# Precision_Arduino_Charlieplex_2_0.net
KiCad netlist of a schematic drawn in EAGLE
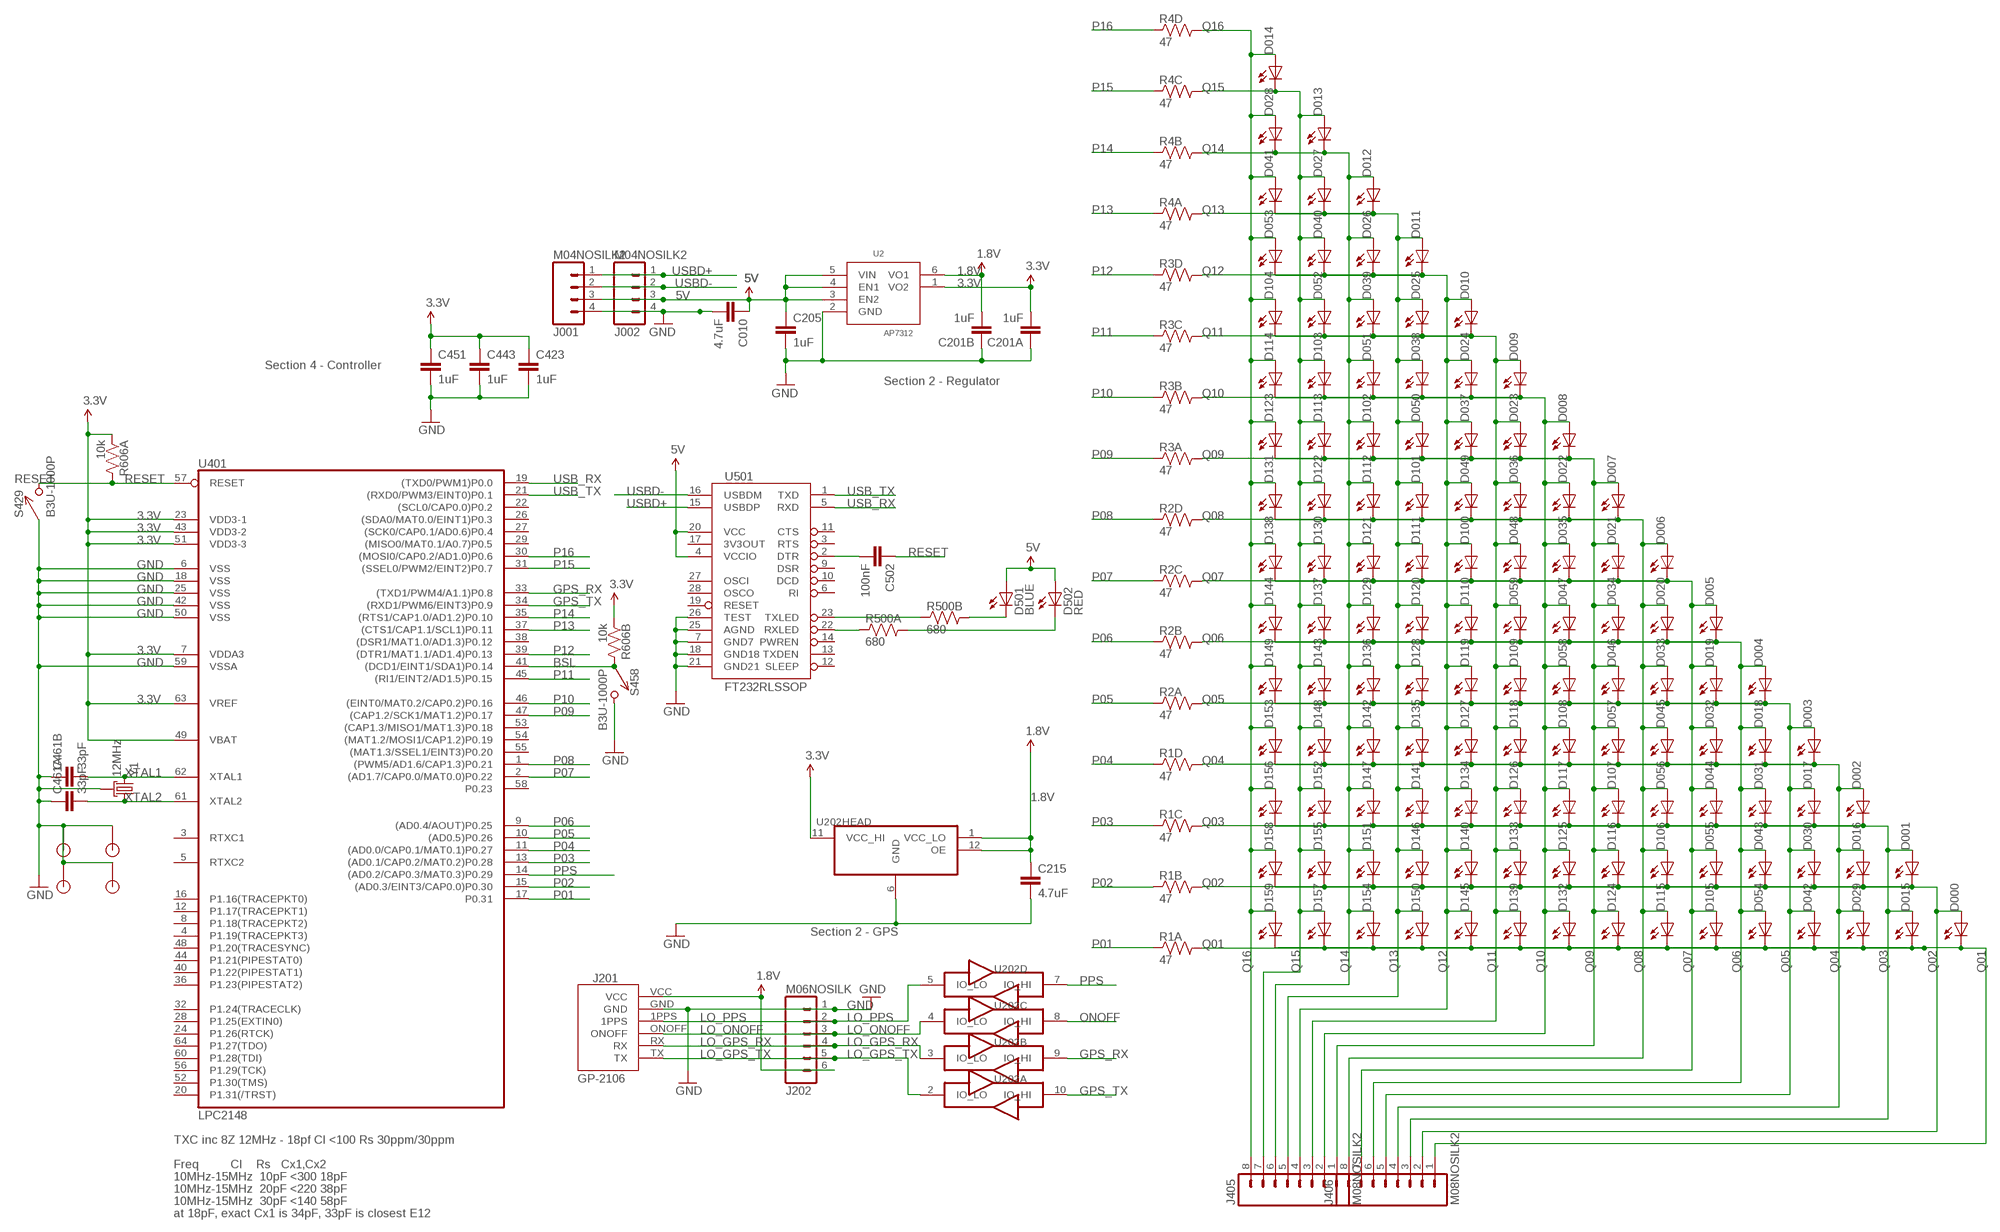
[diagram p0: schematic, sheet 1]

(export (version "E")
  (design (tool "Eeschema 10.0.6"))
  (components
    (comp (ref "C010")
      (value "4.7uF")
      (footprint "eagle-import:0603-CAP")
      (libsource (lib "eagle-import") (part "CAP0603-CAP"))
    )
    (comp (ref "C201")
      (value "1uF")
      (footprint "eagle-import:CKCM25")
      (libsource (lib "eagle-import") (part "CKCM25"))
    )
    (comp (ref "C205")
      (value "1uF")
      (footprint "eagle-import:0603-CAP")
      (libsource (lib "eagle-import") (part "SparkFun-Capacitors_CAP0603-CAP"))
    )
    (comp (ref "C215")
      (value "4.7uF")
      (footprint "eagle-import:0402-CAP")
      (libsource (lib "eagle-import") (part "CAP0402-CAP"))
    )
    (comp (ref "C423")
      (value "1uF")
      (footprint "eagle-import:0603-CAP")
      (libsource (lib "eagle-import") (part "SparkFun-Capacitors_CAP0603-CAP"))
    )
    (comp (ref "C443")
      (value "1uF")
      (footprint "eagle-import:0603-CAP")
      (libsource (lib "eagle-import") (part "SparkFun-Capacitors_CAP0603-CAP"))
    )
    (comp (ref "C451")
      (value "1uF")
      (footprint "eagle-import:0603-CAP")
      (libsource (lib "eagle-import") (part "SparkFun-Capacitors_CAP0603-CAP"))
    )
    (comp (ref "C461")
      (value "33pF")
      (footprint "eagle-import:CKCM25")
      (libsource (lib "eagle-import") (part "CKCM25"))
    )
    (comp (ref "C502")
      (value "100nF")
      (footprint "eagle-import:0603-CAP")
      (libsource (lib "eagle-import") (part "CAP0603-CAP"))
    )
    (comp (ref "D000")
      (value "HOUR")
      (footprint "eagle-import:LED-0603")
      (libsource (lib "eagle-import") (part "LED0603"))
    )
    (comp (ref "D001")
      (value "HOUR")
      (footprint "eagle-import:LED-0603")
      (libsource (lib "eagle-import") (part "LED0603"))
    )
    (comp (ref "D002")
      (value "HOUR")
      (footprint "eagle-import:LED-0603")
      (libsource (lib "eagle-import") (part "LED0603"))
    )
    (comp (ref "D003")
      (value "HOUR")
      (footprint "eagle-import:LED-0603")
      (libsource (lib "eagle-import") (part "LED0603"))
    )
    (comp (ref "D004")
      (value "HOUR")
      (footprint "eagle-import:LED-0603")
      (libsource (lib "eagle-import") (part "LED0603"))
    )
    (comp (ref "D005")
      (value "HOUR")
      (footprint "eagle-import:LED-0603")
      (libsource (lib "eagle-import") (part "LED0603"))
    )
    (comp (ref "D006")
      (value "HOUR")
      (footprint "eagle-import:LED-0603")
      (libsource (lib "eagle-import") (part "LED0603"))
    )
    (comp (ref "D007")
      (value "HOUR")
      (footprint "eagle-import:LED-0603")
      (libsource (lib "eagle-import") (part "LED0603"))
    )
    (comp (ref "D008")
      (value "HOUR")
      (footprint "eagle-import:LED-0603")
      (libsource (lib "eagle-import") (part "LED0603"))
    )
    (comp (ref "D009")
      (value "HOUR")
      (footprint "eagle-import:LED-0603")
      (libsource (lib "eagle-import") (part "LED0603"))
    )
    (comp (ref "D010")
      (value "HOUR")
      (footprint "eagle-import:LED-0603")
      (libsource (lib "eagle-import") (part "LED0603"))
    )
    (comp (ref "D011")
      (value "HOUR")
      (footprint "eagle-import:LED-0603")
      (libsource (lib "eagle-import") (part "LED0603"))
    )
    (comp (ref "D012")
      (value "HOUR")
      (footprint "eagle-import:LED-0603")
      (libsource (lib "eagle-import") (part "LED0603"))
    )
    (comp (ref "D013")
      (value "HOUR")
      (footprint "eagle-import:LED-0603")
      (libsource (lib "eagle-import") (part "LED0603"))
    )
    (comp (ref "D014")
      (value "HOUR")
      (footprint "eagle-import:LED-0603")
      (libsource (lib "eagle-import") (part "LED0603"))
    )
    (comp (ref "D015")
      (value "HOUR")
      (footprint "eagle-import:LED-0603")
      (libsource (lib "eagle-import") (part "LED0603"))
    )
    (comp (ref "D016")
      (value "HOUR")
      (footprint "eagle-import:LED-0603")
      (libsource (lib "eagle-import") (part "LED0603"))
    )
    (comp (ref "D017")
      (value "HOUR")
      (footprint "eagle-import:LED-0603")
      (libsource (lib "eagle-import") (part "LED0603"))
    )
    (comp (ref "D018")
      (value "HOUR")
      (footprint "eagle-import:LED-0603")
      (libsource (lib "eagle-import") (part "LED0603"))
    )
    (comp (ref "D019")
      (value "HOUR")
      (footprint "eagle-import:LED-0603")
      (libsource (lib "eagle-import") (part "LED0603"))
    )
    (comp (ref "D020")
      (value "HOUR")
      (footprint "eagle-import:LED-0603")
      (libsource (lib "eagle-import") (part "LED0603"))
    )
    (comp (ref "D021")
      (value "HOUR")
      (footprint "eagle-import:LED-0603")
      (libsource (lib "eagle-import") (part "LED0603"))
    )
    (comp (ref "D022")
      (value "HOUR")
      (footprint "eagle-import:LED-0603")
      (libsource (lib "eagle-import") (part "LED0603"))
    )
    (comp (ref "D023")
      (value "HOUR")
      (footprint "eagle-import:LED-0603")
      (libsource (lib "eagle-import") (part "LED0603"))
    )
    (comp (ref "D024")
      (value "HOUR")
      (footprint "eagle-import:LED-0603")
      (libsource (lib "eagle-import") (part "LED0603"))
    )
    (comp (ref "D025")
      (value "HOUR")
      (footprint "eagle-import:LED-0603")
      (libsource (lib "eagle-import") (part "LED0603"))
    )
    (comp (ref "D026")
      (value "HOUR")
      (footprint "eagle-import:LED-0603")
      (libsource (lib "eagle-import") (part "LED0603"))
    )
    (comp (ref "D027")
      (value "HOUR")
      (footprint "eagle-import:LED-0603")
      (libsource (lib "eagle-import") (part "LED0603"))
    )
    (comp (ref "D028")
      (value "HOUR")
      (footprint "eagle-import:LED-0603")
      (libsource (lib "eagle-import") (part "LED0603"))
    )
    (comp (ref "D029")
      (value "HOUR")
      (footprint "eagle-import:LED-0603")
      (libsource (lib "eagle-import") (part "LED0603"))
    )
    (comp (ref "D030")
      (value "HOUR")
      (footprint "eagle-import:LED-0603")
      (libsource (lib "eagle-import") (part "LED0603"))
    )
    (comp (ref "D031")
      (value "HOUR")
      (footprint "eagle-import:LED-0603")
      (libsource (lib "eagle-import") (part "LED0603"))
    )
    (comp (ref "D032")
      (value "HOUR")
      (footprint "eagle-import:LED-0603")
      (libsource (lib "eagle-import") (part "LED0603"))
    )
    (comp (ref "D033")
      (value "HOUR")
      (footprint "eagle-import:LED-0603")
      (libsource (lib "eagle-import") (part "LED0603"))
    )
    (comp (ref "D034")
      (value "HOUR")
      (footprint "eagle-import:LED-0603")
      (libsource (lib "eagle-import") (part "LED0603"))
    )
    (comp (ref "D035")
      (value "HOUR")
      (footprint "eagle-import:LED-0603")
      (libsource (lib "eagle-import") (part "LED0603"))
    )
    (comp (ref "D036")
      (value "HOUR")
      (footprint "eagle-import:LED-0603")
      (libsource (lib "eagle-import") (part "LED0603"))
    )
    (comp (ref "D037")
      (value "HOUR")
      (footprint "eagle-import:LED-0603")
      (libsource (lib "eagle-import") (part "LED0603"))
    )
    (comp (ref "D038")
      (value "HOUR")
      (footprint "eagle-import:LED-0603")
      (libsource (lib "eagle-import") (part "LED0603"))
    )
    (comp (ref "D039")
      (value "HOUR")
      (footprint "eagle-import:LED-0603")
      (libsource (lib "eagle-import") (part "LED0603"))
    )
    (comp (ref "D040")
      (value "HOUR")
      (footprint "eagle-import:LED-0603")
      (libsource (lib "eagle-import") (part "LED0603"))
    )
    (comp (ref "D041")
      (value "HOUR")
      (footprint "eagle-import:LED-0603")
      (libsource (lib "eagle-import") (part "LED0603"))
    )
    (comp (ref "D042")
      (value "HOUR")
      (footprint "eagle-import:LED-0603")
      (libsource (lib "eagle-import") (part "LED0603"))
    )
    (comp (ref "D043")
      (value "HOUR")
      (footprint "eagle-import:LED-0603")
      (libsource (lib "eagle-import") (part "LED0603"))
    )
    (comp (ref "D044")
      (value "HOUR")
      (footprint "eagle-import:LED-0603")
      (libsource (lib "eagle-import") (part "LED0603"))
    )
    (comp (ref "D045")
      (value "HOUR")
      (footprint "eagle-import:LED-0603")
      (libsource (lib "eagle-import") (part "LED0603"))
    )
    (comp (ref "D046")
      (value "HOUR")
      (footprint "eagle-import:LED-0603")
      (libsource (lib "eagle-import") (part "LED0603"))
    )
    (comp (ref "D047")
      (value "HOUR")
      (footprint "eagle-import:LED-0603")
      (libsource (lib "eagle-import") (part "LED0603"))
    )
    (comp (ref "D048")
      (value "HOUR")
      (footprint "eagle-import:LED-0603")
      (libsource (lib "eagle-import") (part "LED0603"))
    )
    (comp (ref "D049")
      (value "HOUR")
      (footprint "eagle-import:LED-0603")
      (libsource (lib "eagle-import") (part "LED0603"))
    )
    (comp (ref "D050")
      (value "HOUR")
      (footprint "eagle-import:LED-0603")
      (libsource (lib "eagle-import") (part "LED0603"))
    )
    (comp (ref "D051")
      (value "HOUR")
      (footprint "eagle-import:LED-0603")
      (libsource (lib "eagle-import") (part "LED0603"))
    )
    (comp (ref "D052")
      (value "HOUR")
      (footprint "eagle-import:LED-0603")
      (libsource (lib "eagle-import") (part "LED0603"))
    )
    (comp (ref "D053")
      (value "HOUR")
      (footprint "eagle-import:LED-0603")
      (libsource (lib "eagle-import") (part "LED0603"))
    )
    (comp (ref "D054")
      (value "HOUR")
      (footprint "eagle-import:LED-0603")
      (libsource (lib "eagle-import") (part "LED0603"))
    )
    (comp (ref "D055")
      (value "HOUR")
      (footprint "eagle-import:LED-0603")
      (libsource (lib "eagle-import") (part "LED0603"))
    )
    (comp (ref "D056")
      (value "HOUR")
      (footprint "eagle-import:LED-0603")
      (libsource (lib "eagle-import") (part "LED0603"))
    )
    (comp (ref "D057")
      (value "HOUR")
      (footprint "eagle-import:LED-0603")
      (libsource (lib "eagle-import") (part "LED0603"))
    )
    (comp (ref "D058")
      (value "HOUR")
      (footprint "eagle-import:LED-0603")
      (libsource (lib "eagle-import") (part "LED0603"))
    )
    (comp (ref "D059")
      (value "HOUR")
      (footprint "eagle-import:LED-0603")
      (libsource (lib "eagle-import") (part "LED0603"))
    )
    (comp (ref "D100")
      (value "HOUR")
      (footprint "eagle-import:LED-0603")
      (libsource (lib "eagle-import") (part "LED0603"))
    )
    (comp (ref "D101")
      (value "HOUR")
      (footprint "eagle-import:LED-0603")
      (libsource (lib "eagle-import") (part "LED0603"))
    )
    (comp (ref "D102")
      (value "HOUR")
      (footprint "eagle-import:LED-0603")
      (libsource (lib "eagle-import") (part "LED0603"))
    )
    (comp (ref "D103")
      (value "HOUR")
      (footprint "eagle-import:LED-0603")
      (libsource (lib "eagle-import") (part "LED0603"))
    )
    (comp (ref "D104")
      (value "HOUR")
      (footprint "eagle-import:LED-0603")
      (libsource (lib "eagle-import") (part "LED0603"))
    )
    (comp (ref "D105")
      (value "HOUR")
      (footprint "eagle-import:LED-0603")
      (libsource (lib "eagle-import") (part "LED0603"))
    )
    (comp (ref "D106")
      (value "HOUR")
      (footprint "eagle-import:LED-0603")
      (libsource (lib "eagle-import") (part "LED0603"))
    )
    (comp (ref "D107")
      (value "HOUR")
      (footprint "eagle-import:LED-0603")
      (libsource (lib "eagle-import") (part "LED0603"))
    )
    (comp (ref "D108")
      (value "HOUR")
      (footprint "eagle-import:LED-0603")
      (libsource (lib "eagle-import") (part "LED0603"))
    )
    (comp (ref "D109")
      (value "HOUR")
      (footprint "eagle-import:LED-0603")
      (libsource (lib "eagle-import") (part "LED0603"))
    )
    (comp (ref "D110")
      (value "HOUR")
      (footprint "eagle-import:LED-0603")
      (libsource (lib "eagle-import") (part "LED0603"))
    )
    (comp (ref "D111")
      (value "HOUR")
      (footprint "eagle-import:LED-0603")
      (libsource (lib "eagle-import") (part "LED0603"))
    )
    (comp (ref "D112")
      (value "HOUR")
      (footprint "eagle-import:LED-0603")
      (libsource (lib "eagle-import") (part "LED0603"))
    )
    (comp (ref "D113")
      (value "HOUR")
      (footprint "eagle-import:LED-0603")
      (libsource (lib "eagle-import") (part "LED0603"))
    )
    (comp (ref "D114")
      (value "HOUR")
      (footprint "eagle-import:LED-0603")
      (libsource (lib "eagle-import") (part "LED0603"))
    )
    (comp (ref "D115")
      (value "HOUR")
      (footprint "eagle-import:LED-0603")
      (libsource (lib "eagle-import") (part "LED0603"))
    )
    (comp (ref "D116")
      (value "HOUR")
      (footprint "eagle-import:LED-0603")
      (libsource (lib "eagle-import") (part "LED0603"))
    )
    (comp (ref "D117")
      (value "HOUR")
      (footprint "eagle-import:LED-0603")
      (libsource (lib "eagle-import") (part "LED0603"))
    )
    (comp (ref "D118")
      (value "HOUR")
      (footprint "eagle-import:LED-0603")
      (libsource (lib "eagle-import") (part "LED0603"))
    )
    (comp (ref "D119")
      (value "HOUR")
      (footprint "eagle-import:LED-0603")
      (libsource (lib "eagle-import") (part "LED0603"))
    )
    (comp (ref "D120")
      (value "HOUR")
      (footprint "eagle-import:LED-0603")
      (libsource (lib "eagle-import") (part "LED0603"))
    )
    (comp (ref "D121")
      (value "HOUR")
      (footprint "eagle-import:LED-0603")
      (libsource (lib "eagle-import") (part "LED0603"))
    )
    (comp (ref "D122")
      (value "HOUR")
      (footprint "eagle-import:LED-0603")
      (libsource (lib "eagle-import") (part "LED0603"))
    )
    (comp (ref "D123")
      (value "HOUR")
      (footprint "eagle-import:LED-0603")
      (libsource (lib "eagle-import") (part "LED0603"))
    )
    (comp (ref "D124")
      (value "HOUR")
      (footprint "eagle-import:LED-0603")
      (libsource (lib "eagle-import") (part "LED0603"))
    )
    (comp (ref "D125")
      (value "HOUR")
      (footprint "eagle-import:LED-0603")
      (libsource (lib "eagle-import") (part "LED0603"))
    )
    (comp (ref "D126")
      (value "HOUR")
      (footprint "eagle-import:LED-0603")
      (libsource (lib "eagle-import") (part "LED0603"))
    )
    (comp (ref "D127")
      (value "HOUR")
      (footprint "eagle-import:LED-0603")
      (libsource (lib "eagle-import") (part "LED0603"))
    )
    (comp (ref "D128")
      (value "HOUR")
      (footprint "eagle-import:LED-0603")
      (libsource (lib "eagle-import") (part "LED0603"))
    )
    (comp (ref "D129")
      (value "HOUR")
      (footprint "eagle-import:LED-0603")
      (libsource (lib "eagle-import") (part "LED0603"))
    )
    (comp (ref "D130")
      (value "HOUR")
      (footprint "eagle-import:LED-0603")
      (libsource (lib "eagle-import") (part "LED0603"))
    )
    (comp (ref "D131")
      (value "HOUR")
      (footprint "eagle-import:LED-0603")
      (libsource (lib "eagle-import") (part "LED0603"))
    )
    (comp (ref "D132")
      (value "HOUR")
      (footprint "eagle-import:LED-0603")
      (libsource (lib "eagle-import") (part "LED0603"))
    )
    (comp (ref "D133")
      (value "HOUR")
      (footprint "eagle-import:LED-0603")
      (libsource (lib "eagle-import") (part "LED0603"))
    )
    (comp (ref "D134")
      (value "HOUR")
      (footprint "eagle-import:LED-0603")
      (libsource (lib "eagle-import") (part "LED0603"))
    )
    (comp (ref "D135")
      (value "HOUR")
      (footprint "eagle-import:LED-0603")
      (libsource (lib "eagle-import") (part "LED0603"))
    )
    (comp (ref "D136")
      (value "HOUR")
      (footprint "eagle-import:LED-0603")
      (libsource (lib "eagle-import") (part "LED0603"))
    )
    (comp (ref "D137")
      (value "HOUR")
      (footprint "eagle-import:LED-0603")
      (libsource (lib "eagle-import") (part "LED0603"))
    )
    (comp (ref "D138")
      (value "HOUR")
      (footprint "eagle-import:LED-0603")
      (libsource (lib "eagle-import") (part "LED0603"))
    )
    (comp (ref "D139")
      (value "HOUR")
      (footprint "eagle-import:LED-0603")
      (libsource (lib "eagle-import") (part "LED0603"))
    )
    (comp (ref "D140")
      (value "HOUR")
      (footprint "eagle-import:LED-0603")
      (libsource (lib "eagle-import") (part "LED0603"))
    )
    (comp (ref "D141")
      (value "HOUR")
      (footprint "eagle-import:LED-0603")
      (libsource (lib "eagle-import") (part "LED0603"))
    )
    (comp (ref "D142")
      (value "HOUR")
      (footprint "eagle-import:LED-0603")
      (libsource (lib "eagle-import") (part "LED0603"))
    )
    (comp (ref "D143")
      (value "HOUR")
      (footprint "eagle-import:LED-0603")
      (libsource (lib "eagle-import") (part "LED0603"))
    )
    (comp (ref "D144")
      (value "HOUR")
      (footprint "eagle-import:LED-0603")
      (libsource (lib "eagle-import") (part "LED0603"))
    )
    (comp (ref "D145")
      (value "HOUR")
      (footprint "eagle-import:LED-0603")
      (libsource (lib "eagle-import") (part "LED0603"))
    )
    (comp (ref "D146")
      (value "HOUR")
      (footprint "eagle-import:LED-0603")
      (libsource (lib "eagle-import") (part "LED0603"))
    )
    (comp (ref "D147")
      (value "HOUR")
      (footprint "eagle-import:LED-0603")
      (libsource (lib "eagle-import") (part "LED0603"))
    )
    (comp (ref "D148")
      (value "HOUR")
      (footprint "eagle-import:LED-0603")
      (libsource (lib "eagle-import") (part "LED0603"))
    )
    (comp (ref "D149")
      (value "HOUR")
      (footprint "eagle-import:LED-0603")
      (libsource (lib "eagle-import") (part "LED0603"))
    )
    (comp (ref "D150")
      (value "HOUR")
      (footprint "eagle-import:LED-0603")
      (libsource (lib "eagle-import") (part "LED0603"))
    )
    (comp (ref "D151")
      (value "HOUR")
      (footprint "eagle-import:LED-0603")
      (libsource (lib "eagle-import") (part "LED0603"))
    )
    (comp (ref "D152")
      (value "HOUR")
      (footprint "eagle-import:LED-0603")
      (libsource (lib "eagle-import") (part "LED0603"))
    )
    (comp (ref "D153")
      (value "HOUR")
      (footprint "eagle-import:LED-0603")
      (libsource (lib "eagle-import") (part "LED0603"))
    )
    (comp (ref "D154")
      (value "HOUR")
      (footprint "eagle-import:LED-0603")
      (libsource (lib "eagle-import") (part "LED0603"))
    )
    (comp (ref "D155")
      (value "HOUR")
      (footprint "eagle-import:LED-0603")
      (libsource (lib "eagle-import") (part "LED0603"))
    )
    (comp (ref "D156")
      (value "HOUR")
      (footprint "eagle-import:LED-0603")
      (libsource (lib "eagle-import") (part "LED0603"))
    )
    (comp (ref "D157")
      (value "HOUR")
      (footprint "eagle-import:LED-0603")
      (libsource (lib "eagle-import") (part "LED0603"))
    )
    (comp (ref "D158")
      (value "HOUR")
      (footprint "eagle-import:LED-0603")
      (libsource (lib "eagle-import") (part "LED0603"))
    )
    (comp (ref "D159")
      (value "HOUR")
      (footprint "eagle-import:LED-0603")
      (libsource (lib "eagle-import") (part "LED0603"))
    )
    (comp (ref "D501")
      (value "BLUE")
      (footprint "eagle-import:LED-0603")
      (libsource (lib "eagle-import") (part "LED0603"))
    )
    (comp (ref "D502")
      (value "RED")
      (footprint "eagle-import:LED-0603")
      (libsource (lib "eagle-import") (part "LED0603"))
    )
    (comp (ref "J001")
      (value "M04NOSILK2")
      (footprint "eagle-import:1X04")
      (libsource (lib "eagle-import") (part "M04NOSILK2"))
    )
    (comp (ref "J002")
      (value "M04NOSILK2")
      (footprint "eagle-import:1X04")
      (libsource (lib "eagle-import") (part "M04NOSILK2"))
    )
    (comp (ref "J201")
      (value "GP-2106")
      (footprint "eagle-import:GP-2106")
      (libsource (lib "eagle-import") (part "GP-2106"))
    )
    (comp (ref "J202")
      (value "M06NOSILK")
      (footprint "eagle-import:M06SIP")
      (libsource (lib "eagle-import") (part "M06NOSILK"))
    )
    (comp (ref "J405")
      (value "M08NOSILK2")
      (footprint "eagle-import:1X08")
      (libsource (lib "eagle-import") (part "M08NOSILK2"))
    )
    (comp (ref "J406")
      (value "M08NOSILK2")
      (footprint "eagle-import:1X08")
      (libsource (lib "eagle-import") (part "M08NOSILK2"))
    )
    (comp (ref "JP1")
      (value "STANDOFF")
      (footprint "eagle-import:STANDOFF")
      (libsource (lib "eagle-import") (part "STANDOFF"))
    )
    (comp (ref "JP2")
      (value "STANDOFF")
      (footprint "eagle-import:STANDOFF")
      (libsource (lib "eagle-import") (part "STANDOFF"))
    )
    (comp (ref "JP3")
      (value "STANDOFF")
      (footprint "eagle-import:STANDOFF")
      (libsource (lib "eagle-import") (part "STANDOFF"))
    )
    (comp (ref "JP4")
      (value "STANDOFF")
      (footprint "eagle-import:STANDOFF")
      (libsource (lib "eagle-import") (part "STANDOFF"))
    )
    (comp (ref "R1")
      (value "47")
      (footprint "eagle-import:CRA04")
      (libsource (lib "eagle-import") (part "RP404"))
    )
    (comp (ref "R2")
      (value "47")
      (footprint "eagle-import:CRA04")
      (libsource (lib "eagle-import") (part "RP404"))
    )
    (comp (ref "R3")
      (value "47")
      (footprint "eagle-import:CRA04")
      (libsource (lib "eagle-import") (part "RP404"))
    )
    (comp (ref "R4")
      (value "47")
      (footprint "eagle-import:CRA04")
      (libsource (lib "eagle-import") (part "RP404"))
    )
    (comp (ref "R500")
      (value "680")
      (footprint "eagle-import:CRA02")
      (libsource (lib "eagle-import") (part "RP2EXB24V"))
    )
    (comp (ref "R606")
      (value "10k")
      (footprint "eagle-import:CRA02")
      (libsource (lib "eagle-import") (part "RP2EXB24V"))
    )
    (comp (ref "S429")
      (value "B3U-1000P")
      (footprint "eagle-import:B3U-1000P")
      (libsource (lib "eagle-import") (part "B3U-1000P"))
    )
    (comp (ref "S458")
      (value "B3U-1000P")
      (footprint "eagle-import:B3U-1000P")
      (libsource (lib "eagle-import") (part "B3U-1000P"))
    )
    (comp (ref "U2")
      (value "AP7312")
      (footprint "eagle-import:SOT-23-6")
      (libsource (lib "eagle-import") (part "AP73X2"))
    )
    (comp (ref "U202")
      (value "TXB0104RUT")
      (footprint "eagle-import:R-PUQFN-N12")
      (libsource (lib "eagle-import") (part "TXB0104RUT"))
    )
    (comp (ref "U401")
      (value "LPC2148")
      (footprint "eagle-import:SQFP-S-10X10-64")
      (libsource (lib "eagle-import") (part "LPC213X"))
    )
    (comp (ref "U501")
      (value "FT232RLSSOP")
      (footprint "eagle-import:SSOP28DB")
      (libsource (lib "eagle-import") (part "FT232RLSSOP"))
    )
    (comp (ref "Y1")
      (value "12MHz")
      (footprint "eagle-import:CRYSTAL_SMD_2MM_2_5MM")
      (libsource (lib "eagle-import") (part "CX2520"))
    )
  )
  (nets
    (net (code "1") (name "/BSL") (class "Default")
      (node (ref "R606") (pin "3") (pinfunction "2_3") (pintype "passive"))
      (node (ref "S458") (pin "P$1") (pinfunction "1_P$1") (pintype "bidirectional"))
      (node (ref "U401") (pin "41") (pinfunction "(DCD1/EINT1/SDA1)P0.14_41") (pintype "bidirectional"))
    )
    (net (code "2") (name "/GPS_RX") (class "Default")
      (node (ref "U202") (pin "9") (pinfunction "IO_HI_9") (pintype "bidirectional"))
      (node (ref "U401") (pin "33") (pinfunction "(TXD1/PWM4/A1.1)P0.8_33") (pintype "bidirectional"))
    )
    (net (code "3") (name "/GPS_TX") (class "Default")
      (node (ref "U202") (pin "10") (pinfunction "IO_HI_10") (pintype "bidirectional"))
      (node (ref "U401") (pin "34") (pinfunction "(RXD1/PWM6/EINT3)P0.9_34") (pintype "bidirectional"))
    )
    (net (code "4") (name "/LO_GPS_RX") (class "Default")
      (node (ref "J201") (pin "RX") (pinfunction "RX_RX") (pintype "bidirectional"))
      (node (ref "J202") (pin "4") (pinfunction "4_4") (pintype "passive"))
      (node (ref "U202") (pin "3") (pinfunction "IO_LO_3") (pintype "bidirectional"))
    )
    (net (code "5") (name "/LO_GPS_TX") (class "Default")
      (node (ref "J201") (pin "TX") (pinfunction "TX_TX") (pintype "bidirectional"))
      (node (ref "J202") (pin "5") (pinfunction "5_5") (pintype "passive"))
      (node (ref "U202") (pin "2") (pinfunction "IO_LO_2") (pintype "bidirectional"))
    )
    (net (code "6") (name "/LO_ONOFF") (class "Default")
      (node (ref "J201") (pin "ONOFF") (pinfunction "ONOFF_ONOFF") (pintype "bidirectional"))
      (node (ref "J202") (pin "3") (pinfunction "3_3") (pintype "passive"))
      (node (ref "U202") (pin "4") (pinfunction "IO_LO_4") (pintype "bidirectional"))
    )
    (net (code "7") (name "/LO_PPS") (class "Default")
      (node (ref "J201") (pin "1PPS") (pinfunction "1PPS_1PPS") (pintype "bidirectional"))
      (node (ref "J202") (pin "2") (pinfunction "2_2") (pintype "passive"))
      (node (ref "U202") (pin "5") (pinfunction "IO_LO_5") (pintype "bidirectional"))
    )
    (net (code "8") (name "/ONOFF") (class "Default")
      (node (ref "U202") (pin "8") (pinfunction "IO_HI_8") (pintype "bidirectional"))
    )
    (net (code "9") (name "/P01") (class "Default")
      (node (ref "R1") (pin "1") (pinfunction "1_1") (pintype "passive"))
      (node (ref "U401") (pin "17") (pinfunction "P0.31_17") (pintype "output"))
    )
    (net (code "10") (name "/P02") (class "Default")
      (node (ref "R1") (pin "2") (pinfunction "1_2") (pintype "passive"))
      (node (ref "U401") (pin "15") (pinfunction "(AD0.3/EINT3/CAP0.0)P0.30_15") (pintype "bidirectional"))
    )
    (net (code "11") (name "/P03") (class "Default")
      (node (ref "R1") (pin "3") (pinfunction "1_3") (pintype "passive"))
      (node (ref "U401") (pin "13") (pinfunction "(AD0.1/CAP0.2/MAT0.2)P0.28_13") (pintype "bidirectional"))
    )
    (net (code "12") (name "/P04") (class "Default")
      (node (ref "R1") (pin "4") (pinfunction "1_4") (pintype "passive"))
      (node (ref "U401") (pin "11") (pinfunction "(AD0.0/CAP0.1/MAT0.1)P0.27_11") (pintype "bidirectional"))
    )
    (net (code "13") (name "/P05") (class "Default")
      (node (ref "R2") (pin "1") (pinfunction "1_1") (pintype "passive"))
      (node (ref "U401") (pin "10") (pinfunction "(AD0.5)P0.26_10") (pintype "bidirectional"))
    )
    (net (code "14") (name "/P06") (class "Default")
      (node (ref "R2") (pin "2") (pinfunction "1_2") (pintype "passive"))
      (node (ref "U401") (pin "9") (pinfunction "(AD0.4/AOUT)P0.25_9") (pintype "bidirectional"))
    )
    (net (code "15") (name "/P07") (class "Default")
      (node (ref "R2") (pin "3") (pinfunction "1_3") (pintype "passive"))
      (node (ref "U401") (pin "2") (pinfunction "(AD1.7/CAP0.0/MAT0.0)P0.22_2") (pintype "bidirectional"))
    )
    (net (code "16") (name "/P08") (class "Default")
      (node (ref "R2") (pin "4") (pinfunction "1_4") (pintype "passive"))
      (node (ref "U401") (pin "1") (pinfunction "(PWM5/AD1.6/CAP1.3)P0.21_1") (pintype "bidirectional"))
    )
    (net (code "17") (name "/P09") (class "Default")
      (node (ref "R3") (pin "1") (pinfunction "1_1") (pintype "passive"))
      (node (ref "U401") (pin "47") (pinfunction "(CAP1.2/SCK1/MAT1.2)P0.17_47") (pintype "bidirectional"))
    )
    (net (code "18") (name "/P10") (class "Default")
      (node (ref "R3") (pin "2") (pinfunction "1_2") (pintype "passive"))
      (node (ref "U401") (pin "46") (pinfunction "(EINT0/MAT0.2/CAP0.2)P0.16_46") (pintype "bidirectional"))
    )
    (net (code "19") (name "/P11") (class "Default")
      (node (ref "R3") (pin "3") (pinfunction "1_3") (pintype "passive"))
      (node (ref "U401") (pin "45") (pinfunction "(RI1/EINT2/AD1.5)P0.15_45") (pintype "bidirectional"))
    )
    (net (code "20") (name "/P12") (class "Default")
      (node (ref "R3") (pin "4") (pinfunction "1_4") (pintype "passive"))
      (node (ref "U401") (pin "39") (pinfunction "(DTR1/MAT1.1/AD1.4)P0.13_39") (pintype "bidirectional"))
    )
    (net (code "21") (name "/P13") (class "Default")
      (node (ref "R4") (pin "1") (pinfunction "1_1") (pintype "passive"))
      (node (ref "U401") (pin "37") (pinfunction "(CTS1/CAP1.1/SCL1)P0.11_37") (pintype "bidirectional"))
    )
    (net (code "22") (name "/P14") (class "Default")
      (node (ref "R4") (pin "2") (pinfunction "1_2") (pintype "passive"))
      (node (ref "U401") (pin "35") (pinfunction "(RTS1/CAP1.0/AD1.2)P0.10_35") (pintype "bidirectional"))
    )
    (net (code "23") (name "/P15") (class "Default")
      (node (ref "R4") (pin "3") (pinfunction "1_3") (pintype "passive"))
      (node (ref "U401") (pin "31") (pinfunction "(SSEL0/PWM2/EINT2)P0.7_31") (pintype "bidirectional"))
    )
    (net (code "24") (name "/P16") (class "Default")
      (node (ref "R4") (pin "4") (pinfunction "1_4") (pintype "passive"))
      (node (ref "U401") (pin "30") (pinfunction "(MOSI0/CAP0.2/AD1.0)P0.6_30") (pintype "bidirectional"))
    )
    (net (code "25") (name "/PPS") (class "Default")
      (node (ref "U202") (pin "7") (pinfunction "IO_HI_7") (pintype "bidirectional"))
      (node (ref "U401") (pin "14") (pinfunction "(AD0.2/CAP0.3/MAT0.3)P0.29_14") (pintype "bidirectional"))
    )
    (net (code "26") (name "/Q01") (class "Default")
      (node (ref "D000") (pin "C") (pinfunction "C_C") (pintype "passive"))
      (node (ref "D015") (pin "C") (pinfunction "C_C") (pintype "passive"))
      (node (ref "D029") (pin "C") (pinfunction "C_C") (pintype "passive"))
      (node (ref "D042") (pin "C") (pinfunction "C_C") (pintype "passive"))
      (node (ref "D054") (pin "C") (pinfunction "C_C") (pintype "passive"))
      (node (ref "D105") (pin "C") (pinfunction "C_C") (pintype "passive"))
      (node (ref "D115") (pin "C") (pinfunction "C_C") (pintype "passive"))
      (node (ref "D124") (pin "C") (pinfunction "C_C") (pintype "passive"))
      (node (ref "D132") (pin "C") (pinfunction "C_C") (pintype "passive"))
      (node (ref "D139") (pin "C") (pinfunction "C_C") (pintype "passive"))
      (node (ref "D145") (pin "C") (pinfunction "C_C") (pintype "passive"))
      (node (ref "D150") (pin "C") (pinfunction "C_C") (pintype "passive"))
      (node (ref "D154") (pin "C") (pinfunction "C_C") (pintype "passive"))
      (node (ref "D157") (pin "C") (pinfunction "C_C") (pintype "passive"))
      (node (ref "D159") (pin "C") (pinfunction "C_C") (pintype "passive"))
      (node (ref "J406") (pin "1") (pinfunction "1_1") (pintype "passive"))
      (node (ref "R1") (pin "8") (pinfunction "2_8") (pintype "passive"))
    )
    (net (code "27") (name "/Q02") (class "Default")
      (node (ref "D000") (pin "A") (pinfunction "A_A") (pintype "passive"))
      (node (ref "D001") (pin "C") (pinfunction "C_C") (pintype "passive"))
      (node (ref "D016") (pin "C") (pinfunction "C_C") (pintype "passive"))
      (node (ref "D030") (pin "C") (pinfunction "C_C") (pintype "passive"))
      (node (ref "D043") (pin "C") (pinfunction "C_C") (pintype "passive"))
      (node (ref "D055") (pin "C") (pinfunction "C_C") (pintype "passive"))
      (node (ref "D106") (pin "C") (pinfunction "C_C") (pintype "passive"))
      (node (ref "D116") (pin "C") (pinfunction "C_C") (pintype "passive"))
      (node (ref "D125") (pin "C") (pinfunction "C_C") (pintype "passive"))
      (node (ref "D133") (pin "C") (pinfunction "C_C") (pintype "passive"))
      (node (ref "D140") (pin "C") (pinfunction "C_C") (pintype "passive"))
      (node (ref "D146") (pin "C") (pinfunction "C_C") (pintype "passive"))
      (node (ref "D151") (pin "C") (pinfunction "C_C") (pintype "passive"))
      (node (ref "D155") (pin "C") (pinfunction "C_C") (pintype "passive"))
      (node (ref "D158") (pin "C") (pinfunction "C_C") (pintype "passive"))
      (node (ref "J406") (pin "2") (pinfunction "2_2") (pintype "passive"))
      (node (ref "R1") (pin "7") (pinfunction "2_7") (pintype "passive"))
    )
    (net (code "28") (name "/Q03") (class "Default")
      (node (ref "D001") (pin "A") (pinfunction "A_A") (pintype "passive"))
      (node (ref "D002") (pin "C") (pinfunction "C_C") (pintype "passive"))
      (node (ref "D015") (pin "A") (pinfunction "A_A") (pintype "passive"))
      (node (ref "D017") (pin "C") (pinfunction "C_C") (pintype "passive"))
      (node (ref "D031") (pin "C") (pinfunction "C_C") (pintype "passive"))
      (node (ref "D044") (pin "C") (pinfunction "C_C") (pintype "passive"))
      (node (ref "D056") (pin "C") (pinfunction "C_C") (pintype "passive"))
      (node (ref "D107") (pin "C") (pinfunction "C_C") (pintype "passive"))
      (node (ref "D117") (pin "C") (pinfunction "C_C") (pintype "passive"))
      (node (ref "D126") (pin "C") (pinfunction "C_C") (pintype "passive"))
      (node (ref "D134") (pin "C") (pinfunction "C_C") (pintype "passive"))
      (node (ref "D141") (pin "C") (pinfunction "C_C") (pintype "passive"))
      (node (ref "D147") (pin "C") (pinfunction "C_C") (pintype "passive"))
      (node (ref "D152") (pin "C") (pinfunction "C_C") (pintype "passive"))
      (node (ref "D156") (pin "C") (pinfunction "C_C") (pintype "passive"))
      (node (ref "J406") (pin "3") (pinfunction "3_3") (pintype "passive"))
      (node (ref "R1") (pin "6") (pinfunction "2_6") (pintype "passive"))
    )
    (net (code "29") (name "/Q04") (class "Default")
      (node (ref "D002") (pin "A") (pinfunction "A_A") (pintype "passive"))
      (node (ref "D003") (pin "C") (pinfunction "C_C") (pintype "passive"))
      (node (ref "D016") (pin "A") (pinfunction "A_A") (pintype "passive"))
      (node (ref "D018") (pin "C") (pinfunction "C_C") (pintype "passive"))
      (node (ref "D029") (pin "A") (pinfunction "A_A") (pintype "passive"))
      (node (ref "D032") (pin "C") (pinfunction "C_C") (pintype "passive"))
      (node (ref "D045") (pin "C") (pinfunction "C_C") (pintype "passive"))
      (node (ref "D057") (pin "C") (pinfunction "C_C") (pintype "passive"))
      (node (ref "D108") (pin "C") (pinfunction "C_C") (pintype "passive"))
      (node (ref "D118") (pin "C") (pinfunction "C_C") (pintype "passive"))
      (node (ref "D127") (pin "C") (pinfunction "C_C") (pintype "passive"))
      (node (ref "D135") (pin "C") (pinfunction "C_C") (pintype "passive"))
      (node (ref "D142") (pin "C") (pinfunction "C_C") (pintype "passive"))
      (node (ref "D148") (pin "C") (pinfunction "C_C") (pintype "passive"))
      (node (ref "D153") (pin "C") (pinfunction "C_C") (pintype "passive"))
      (node (ref "J406") (pin "4") (pinfunction "4_4") (pintype "passive"))
      (node (ref "R1") (pin "5") (pinfunction "2_5") (pintype "passive"))
    )
    (net (code "30") (name "/Q05") (class "Default")
      (node (ref "D003") (pin "A") (pinfunction "A_A") (pintype "passive"))
      (node (ref "D004") (pin "C") (pinfunction "C_C") (pintype "passive"))
      (node (ref "D017") (pin "A") (pinfunction "A_A") (pintype "passive"))
      (node (ref "D019") (pin "C") (pinfunction "C_C") (pintype "passive"))
      (node (ref "D030") (pin "A") (pinfunction "A_A") (pintype "passive"))
      (node (ref "D033") (pin "C") (pinfunction "C_C") (pintype "passive"))
      (node (ref "D042") (pin "A") (pinfunction "A_A") (pintype "passive"))
      (node (ref "D046") (pin "C") (pinfunction "C_C") (pintype "passive"))
      (node (ref "D058") (pin "C") (pinfunction "C_C") (pintype "passive"))
      (node (ref "D109") (pin "C") (pinfunction "C_C") (pintype "passive"))
      (node (ref "D119") (pin "C") (pinfunction "C_C") (pintype "passive"))
      (node (ref "D128") (pin "C") (pinfunction "C_C") (pintype "passive"))
      (node (ref "D136") (pin "C") (pinfunction "C_C") (pintype "passive"))
      (node (ref "D143") (pin "C") (pinfunction "C_C") (pintype "passive"))
      (node (ref "D149") (pin "C") (pinfunction "C_C") (pintype "passive"))
      (node (ref "J406") (pin "5") (pinfunction "5_5") (pintype "passive"))
      (node (ref "R2") (pin "8") (pinfunction "2_8") (pintype "passive"))
    )
    (net (code "31") (name "/Q06") (class "Default")
      (node (ref "D004") (pin "A") (pinfunction "A_A") (pintype "passive"))
      (node (ref "D005") (pin "C") (pinfunction "C_C") (pintype "passive"))
      (node (ref "D018") (pin "A") (pinfunction "A_A") (pintype "passive"))
      (node (ref "D020") (pin "C") (pinfunction "C_C") (pintype "passive"))
      (node (ref "D031") (pin "A") (pinfunction "A_A") (pintype "passive"))
      (node (ref "D034") (pin "C") (pinfunction "C_C") (pintype "passive"))
      (node (ref "D043") (pin "A") (pinfunction "A_A") (pintype "passive"))
      (node (ref "D047") (pin "C") (pinfunction "C_C") (pintype "passive"))
      (node (ref "D054") (pin "A") (pinfunction "A_A") (pintype "passive"))
      (node (ref "D059") (pin "C") (pinfunction "C_C") (pintype "passive"))
      (node (ref "D110") (pin "C") (pinfunction "C_C") (pintype "passive"))
      (node (ref "D120") (pin "C") (pinfunction "C_C") (pintype "passive"))
      (node (ref "D129") (pin "C") (pinfunction "C_C") (pintype "passive"))
      (node (ref "D137") (pin "C") (pinfunction "C_C") (pintype "passive"))
      (node (ref "D144") (pin "C") (pinfunction "C_C") (pintype "passive"))
      (node (ref "J406") (pin "6") (pinfunction "6_6") (pintype "passive"))
      (node (ref "R2") (pin "7") (pinfunction "2_7") (pintype "passive"))
    )
    (net (code "32") (name "/Q07") (class "Default")
      (node (ref "D005") (pin "A") (pinfunction "A_A") (pintype "passive"))
      (node (ref "D006") (pin "C") (pinfunction "C_C") (pintype "passive"))
      (node (ref "D019") (pin "A") (pinfunction "A_A") (pintype "passive"))
      (node (ref "D021") (pin "C") (pinfunction "C_C") (pintype "passive"))
      (node (ref "D032") (pin "A") (pinfunction "A_A") (pintype "passive"))
      (node (ref "D035") (pin "C") (pinfunction "C_C") (pintype "passive"))
      (node (ref "D044") (pin "A") (pinfunction "A_A") (pintype "passive"))
      (node (ref "D048") (pin "C") (pinfunction "C_C") (pintype "passive"))
      (node (ref "D055") (pin "A") (pinfunction "A_A") (pintype "passive"))
      (node (ref "D100") (pin "C") (pinfunction "C_C") (pintype "passive"))
      (node (ref "D105") (pin "A") (pinfunction "A_A") (pintype "passive"))
      (node (ref "D111") (pin "C") (pinfunction "C_C") (pintype "passive"))
      (node (ref "D121") (pin "C") (pinfunction "C_C") (pintype "passive"))
      (node (ref "D130") (pin "C") (pinfunction "C_C") (pintype "passive"))
      (node (ref "D138") (pin "C") (pinfunction "C_C") (pintype "passive"))
      (node (ref "J406") (pin "7") (pinfunction "7_7") (pintype "passive"))
      (node (ref "R2") (pin "6") (pinfunction "2_6") (pintype "passive"))
    )
    (net (code "33") (name "/Q08") (class "Default")
      (node (ref "D006") (pin "A") (pinfunction "A_A") (pintype "passive"))
      (node (ref "D007") (pin "C") (pinfunction "C_C") (pintype "passive"))
      (node (ref "D020") (pin "A") (pinfunction "A_A") (pintype "passive"))
      (node (ref "D022") (pin "C") (pinfunction "C_C") (pintype "passive"))
      (node (ref "D033") (pin "A") (pinfunction "A_A") (pintype "passive"))
      (node (ref "D036") (pin "C") (pinfunction "C_C") (pintype "passive"))
      (node (ref "D045") (pin "A") (pinfunction "A_A") (pintype "passive"))
      (node (ref "D049") (pin "C") (pinfunction "C_C") (pintype "passive"))
      (node (ref "D056") (pin "A") (pinfunction "A_A") (pintype "passive"))
      (node (ref "D101") (pin "C") (pinfunction "C_C") (pintype "passive"))
      (node (ref "D106") (pin "A") (pinfunction "A_A") (pintype "passive"))
      (node (ref "D112") (pin "C") (pinfunction "C_C") (pintype "passive"))
      (node (ref "D115") (pin "A") (pinfunction "A_A") (pintype "passive"))
      (node (ref "D122") (pin "C") (pinfunction "C_C") (pintype "passive"))
      (node (ref "D131") (pin "C") (pinfunction "C_C") (pintype "passive"))
      (node (ref "J406") (pin "8") (pinfunction "8_8") (pintype "passive"))
      (node (ref "R2") (pin "5") (pinfunction "2_5") (pintype "passive"))
    )
    (net (code "34") (name "/Q09") (class "Default")
      (node (ref "D007") (pin "A") (pinfunction "A_A") (pintype "passive"))
      (node (ref "D008") (pin "C") (pinfunction "C_C") (pintype "passive"))
      (node (ref "D021") (pin "A") (pinfunction "A_A") (pintype "passive"))
      (node (ref "D023") (pin "C") (pinfunction "C_C") (pintype "passive"))
      (node (ref "D034") (pin "A") (pinfunction "A_A") (pintype "passive"))
      (node (ref "D037") (pin "C") (pinfunction "C_C") (pintype "passive"))
      (node (ref "D046") (pin "A") (pinfunction "A_A") (pintype "passive"))
      (node (ref "D050") (pin "C") (pinfunction "C_C") (pintype "passive"))
      (node (ref "D057") (pin "A") (pinfunction "A_A") (pintype "passive"))
      (node (ref "D102") (pin "C") (pinfunction "C_C") (pintype "passive"))
      (node (ref "D107") (pin "A") (pinfunction "A_A") (pintype "passive"))
      (node (ref "D113") (pin "C") (pinfunction "C_C") (pintype "passive"))
      (node (ref "D116") (pin "A") (pinfunction "A_A") (pintype "passive"))
      (node (ref "D123") (pin "C") (pinfunction "C_C") (pintype "passive"))
      (node (ref "D124") (pin "A") (pinfunction "A_A") (pintype "passive"))
      (node (ref "J405") (pin "1") (pinfunction "1_1") (pintype "passive"))
      (node (ref "R3") (pin "8") (pinfunction "2_8") (pintype "passive"))
    )
    (net (code "35") (name "/Q10") (class "Default")
      (node (ref "D008") (pin "A") (pinfunction "A_A") (pintype "passive"))
      (node (ref "D009") (pin "C") (pinfunction "C_C") (pintype "passive"))
      (node (ref "D022") (pin "A") (pinfunction "A_A") (pintype "passive"))
      (node (ref "D024") (pin "C") (pinfunction "C_C") (pintype "passive"))
      (node (ref "D035") (pin "A") (pinfunction "A_A") (pintype "passive"))
      (node (ref "D038") (pin "C") (pinfunction "C_C") (pintype "passive"))
      (node (ref "D047") (pin "A") (pinfunction "A_A") (pintype "passive"))
      (node (ref "D051") (pin "C") (pinfunction "C_C") (pintype "passive"))
      (node (ref "D058") (pin "A") (pinfunction "A_A") (pintype "passive"))
      (node (ref "D103") (pin "C") (pinfunction "C_C") (pintype "passive"))
      (node (ref "D108") (pin "A") (pinfunction "A_A") (pintype "passive"))
      (node (ref "D114") (pin "C") (pinfunction "C_C") (pintype "passive"))
      (node (ref "D117") (pin "A") (pinfunction "A_A") (pintype "passive"))
      (node (ref "D125") (pin "A") (pinfunction "A_A") (pintype "passive"))
      (node (ref "D132") (pin "A") (pinfunction "A_A") (pintype "passive"))
      (node (ref "J405") (pin "2") (pinfunction "2_2") (pintype "passive"))
      (node (ref "R3") (pin "7") (pinfunction "2_7") (pintype "passive"))
    )
    (net (code "36") (name "/Q11") (class "Default")
      (node (ref "D009") (pin "A") (pinfunction "A_A") (pintype "passive"))
      (node (ref "D010") (pin "C") (pinfunction "C_C") (pintype "passive"))
      (node (ref "D023") (pin "A") (pinfunction "A_A") (pintype "passive"))
      (node (ref "D025") (pin "C") (pinfunction "C_C") (pintype "passive"))
      (node (ref "D036") (pin "A") (pinfunction "A_A") (pintype "passive"))
      (node (ref "D039") (pin "C") (pinfunction "C_C") (pintype "passive"))
      (node (ref "D048") (pin "A") (pinfunction "A_A") (pintype "passive"))
      (node (ref "D052") (pin "C") (pinfunction "C_C") (pintype "passive"))
      (node (ref "D059") (pin "A") (pinfunction "A_A") (pintype "passive"))
      (node (ref "D104") (pin "C") (pinfunction "C_C") (pintype "passive"))
      (node (ref "D109") (pin "A") (pinfunction "A_A") (pintype "passive"))
      (node (ref "D118") (pin "A") (pinfunction "A_A") (pintype "passive"))
      (node (ref "D126") (pin "A") (pinfunction "A_A") (pintype "passive"))
      (node (ref "D133") (pin "A") (pinfunction "A_A") (pintype "passive"))
      (node (ref "D139") (pin "A") (pinfunction "A_A") (pintype "passive"))
      (node (ref "J405") (pin "3") (pinfunction "3_3") (pintype "passive"))
      (node (ref "R3") (pin "6") (pinfunction "2_6") (pintype "passive"))
    )
    (net (code "37") (name "/Q12") (class "Default")
      (node (ref "D010") (pin "A") (pinfunction "A_A") (pintype "passive"))
      (node (ref "D011") (pin "C") (pinfunction "C_C") (pintype "passive"))
      (node (ref "D024") (pin "A") (pinfunction "A_A") (pintype "passive"))
      (node (ref "D026") (pin "C") (pinfunction "C_C") (pintype "passive"))
      (node (ref "D037") (pin "A") (pinfunction "A_A") (pintype "passive"))
      (node (ref "D040") (pin "C") (pinfunction "C_C") (pintype "passive"))
      (node (ref "D049") (pin "A") (pinfunction "A_A") (pintype "passive"))
      (node (ref "D053") (pin "C") (pinfunction "C_C") (pintype "passive"))
      (node (ref "D100") (pin "A") (pinfunction "A_A") (pintype "passive"))
      (node (ref "D110") (pin "A") (pinfunction "A_A") (pintype "passive"))
      (node (ref "D119") (pin "A") (pinfunction "A_A") (pintype "passive"))
      (node (ref "D127") (pin "A") (pinfunction "A_A") (pintype "passive"))
      (node (ref "D134") (pin "A") (pinfunction "A_A") (pintype "passive"))
      (node (ref "D140") (pin "A") (pinfunction "A_A") (pintype "passive"))
      (node (ref "D145") (pin "A") (pinfunction "A_A") (pintype "passive"))
      (node (ref "J405") (pin "4") (pinfunction "4_4") (pintype "passive"))
      (node (ref "R3") (pin "5") (pinfunction "2_5") (pintype "passive"))
    )
    (net (code "38") (name "/Q13") (class "Default")
      (node (ref "D011") (pin "A") (pinfunction "A_A") (pintype "passive"))
      (node (ref "D012") (pin "C") (pinfunction "C_C") (pintype "passive"))
      (node (ref "D025") (pin "A") (pinfunction "A_A") (pintype "passive"))
      (node (ref "D027") (pin "C") (pinfunction "C_C") (pintype "passive"))
      (node (ref "D038") (pin "A") (pinfunction "A_A") (pintype "passive"))
      (node (ref "D041") (pin "C") (pinfunction "C_C") (pintype "passive"))
      (node (ref "D050") (pin "A") (pinfunction "A_A") (pintype "passive"))
      (node (ref "D101") (pin "A") (pinfunction "A_A") (pintype "passive"))
      (node (ref "D111") (pin "A") (pinfunction "A_A") (pintype "passive"))
      (node (ref "D120") (pin "A") (pinfunction "A_A") (pintype "passive"))
      (node (ref "D128") (pin "A") (pinfunction "A_A") (pintype "passive"))
      (node (ref "D135") (pin "A") (pinfunction "A_A") (pintype "passive"))
      (node (ref "D141") (pin "A") (pinfunction "A_A") (pintype "passive"))
      (node (ref "D146") (pin "A") (pinfunction "A_A") (pintype "passive"))
      (node (ref "D150") (pin "A") (pinfunction "A_A") (pintype "passive"))
      (node (ref "J405") (pin "5") (pinfunction "5_5") (pintype "passive"))
      (node (ref "R4") (pin "8") (pinfunction "2_8") (pintype "passive"))
    )
    (net (code "39") (name "/Q14") (class "Default")
      (node (ref "D012") (pin "A") (pinfunction "A_A") (pintype "passive"))
      (node (ref "D013") (pin "C") (pinfunction "C_C") (pintype "passive"))
      (node (ref "D026") (pin "A") (pinfunction "A_A") (pintype "passive"))
      (node (ref "D028") (pin "C") (pinfunction "C_C") (pintype "passive"))
      (node (ref "D039") (pin "A") (pinfunction "A_A") (pintype "passive"))
      (node (ref "D051") (pin "A") (pinfunction "A_A") (pintype "passive"))
      (node (ref "D102") (pin "A") (pinfunction "A_A") (pintype "passive"))
      (node (ref "D112") (pin "A") (pinfunction "A_A") (pintype "passive"))
      (node (ref "D121") (pin "A") (pinfunction "A_A") (pintype "passive"))
      (node (ref "D129") (pin "A") (pinfunction "A_A") (pintype "passive"))
      (node (ref "D136") (pin "A") (pinfunction "A_A") (pintype "passive"))
      (node (ref "D142") (pin "A") (pinfunction "A_A") (pintype "passive"))
      (node (ref "D147") (pin "A") (pinfunction "A_A") (pintype "passive"))
      (node (ref "D151") (pin "A") (pinfunction "A_A") (pintype "passive"))
      (node (ref "D154") (pin "A") (pinfunction "A_A") (pintype "passive"))
      (node (ref "J405") (pin "6") (pinfunction "6_6") (pintype "passive"))
      (node (ref "R4") (pin "7") (pinfunction "2_7") (pintype "passive"))
    )
    (net (code "40") (name "/Q15") (class "Default")
      (node (ref "D013") (pin "A") (pinfunction "A_A") (pintype "passive"))
      (node (ref "D014") (pin "C") (pinfunction "C_C") (pintype "passive"))
      (node (ref "D027") (pin "A") (pinfunction "A_A") (pintype "passive"))
      (node (ref "D040") (pin "A") (pinfunction "A_A") (pintype "passive"))
      (node (ref "D052") (pin "A") (pinfunction "A_A") (pintype "passive"))
      (node (ref "D103") (pin "A") (pinfunction "A_A") (pintype "passive"))
      (node (ref "D113") (pin "A") (pinfunction "A_A") (pintype "passive"))
      (node (ref "D122") (pin "A") (pinfunction "A_A") (pintype "passive"))
      (node (ref "D130") (pin "A") (pinfunction "A_A") (pintype "passive"))
      (node (ref "D137") (pin "A") (pinfunction "A_A") (pintype "passive"))
      (node (ref "D143") (pin "A") (pinfunction "A_A") (pintype "passive"))
      (node (ref "D148") (pin "A") (pinfunction "A_A") (pintype "passive"))
      (node (ref "D152") (pin "A") (pinfunction "A_A") (pintype "passive"))
      (node (ref "D155") (pin "A") (pinfunction "A_A") (pintype "passive"))
      (node (ref "D157") (pin "A") (pinfunction "A_A") (pintype "passive"))
      (node (ref "J405") (pin "7") (pinfunction "7_7") (pintype "passive"))
      (node (ref "R4") (pin "6") (pinfunction "2_6") (pintype "passive"))
    )
    (net (code "41") (name "/Q16") (class "Default")
      (node (ref "D014") (pin "A") (pinfunction "A_A") (pintype "passive"))
      (node (ref "D028") (pin "A") (pinfunction "A_A") (pintype "passive"))
      (node (ref "D041") (pin "A") (pinfunction "A_A") (pintype "passive"))
      (node (ref "D053") (pin "A") (pinfunction "A_A") (pintype "passive"))
      (node (ref "D104") (pin "A") (pinfunction "A_A") (pintype "passive"))
      (node (ref "D114") (pin "A") (pinfunction "A_A") (pintype "passive"))
      (node (ref "D123") (pin "A") (pinfunction "A_A") (pintype "passive"))
      (node (ref "D131") (pin "A") (pinfunction "A_A") (pintype "passive"))
      (node (ref "D138") (pin "A") (pinfunction "A_A") (pintype "passive"))
      (node (ref "D144") (pin "A") (pinfunction "A_A") (pintype "passive"))
      (node (ref "D149") (pin "A") (pinfunction "A_A") (pintype "passive"))
      (node (ref "D153") (pin "A") (pinfunction "A_A") (pintype "passive"))
      (node (ref "D156") (pin "A") (pinfunction "A_A") (pintype "passive"))
      (node (ref "D158") (pin "A") (pinfunction "A_A") (pintype "passive"))
      (node (ref "D159") (pin "A") (pinfunction "A_A") (pintype "passive"))
      (node (ref "J405") (pin "8") (pinfunction "8_8") (pintype "passive"))
      (node (ref "R4") (pin "5") (pinfunction "2_5") (pintype "passive"))
    )
    (net (code "42") (name "/RESET") (class "Default")
      (node (ref "C502") (pin "1") (pinfunction "1_1") (pintype "passive"))
      (node (ref "R606") (pin "4") (pinfunction "2_4") (pintype "passive"))
      (node (ref "S429") (pin "P$2") (pinfunction "2_P$2") (pintype "bidirectional"))
      (node (ref "U401") (pin "57") (pinfunction "RESET_57") (pintype "input"))
    )
    (net (code "43") (name "/USBD+") (class "Default")
      (node (ref "J001") (pin "1") (pinfunction "1_1") (pintype "passive"))
      (node (ref "J002") (pin "1") (pinfunction "1_1") (pintype "passive"))
      (node (ref "U501") (pin "15") (pinfunction "USBDP_15") (pintype "bidirectional"))
    )
    (net (code "44") (name "/USBD-") (class "Default")
      (node (ref "J001") (pin "2") (pinfunction "2_2") (pintype "passive"))
      (node (ref "J002") (pin "2") (pinfunction "2_2") (pintype "passive"))
      (node (ref "U501") (pin "16") (pinfunction "USBDM_16") (pintype "bidirectional"))
    )
    (net (code "45") (name "/USB_RX") (class "Default")
      (node (ref "U401") (pin "19") (pinfunction "(TXD0/PWM1)P0.0_19") (pintype "bidirectional"))
      (node (ref "U501") (pin "5") (pinfunction "RXD_5") (pintype "input"))
    )
    (net (code "46") (name "/USB_TX") (class "Default")
      (node (ref "U401") (pin "21") (pinfunction "(RXD0/PWM3/EINT0)P0.1_21") (pintype "bidirectional"))
      (node (ref "U501") (pin "1") (pinfunction "TXD_1") (pintype "output"))
    )
    (net (code "47") (name "/XTAL1") (class "Default")
      (node (ref "C461") (pin "3") (pinfunction "2_3") (pintype "passive"))
      (node (ref "U401") (pin "62") (pinfunction "XTAL1_62") (pintype "input"))
      (node (ref "Y1") (pin "3") (pinfunction "2_3") (pintype "passive"))
    )
    (net (code "48") (name "/XTAL2") (class "Default")
      (node (ref "C461") (pin "4") (pinfunction "2_4") (pintype "passive"))
      (node (ref "U401") (pin "61") (pinfunction "XTAL2_61") (pintype "output"))
      (node (ref "Y1") (pin "1") (pinfunction "1_1") (pintype "passive"))
    )
    (net (code "49") (name "1.8V") (class "Default")
      (node (ref "C201") (pin "3") (pinfunction "2_3") (pintype "passive"))
      (node (ref "C215") (pin "1") (pinfunction "1_1") (pintype "passive"))
      (node (ref "J201") (pin "VCC") (pinfunction "VCC_VCC") (pintype "bidirectional"))
      (node (ref "J202") (pin "6") (pinfunction "6_6") (pintype "passive"))
      (node (ref "U2") (pin "6") (pinfunction "VO1_6") (pintype "bidirectional"))
      (node (ref "U202") (pin "1") (pinfunction "VCC_LO_1") (pintype "power_in"))
      (node (ref "U202") (pin "12") (pinfunction "OE_12") (pintype "bidirectional"))
    )
    (net (code "50") (name "3.3V") (class "Default")
      (node (ref "C201") (pin "4") (pinfunction "2_4") (pintype "passive"))
      (node (ref "C423") (pin "1") (pinfunction "1_1") (pintype "passive"))
      (node (ref "C443") (pin "1") (pinfunction "1_1") (pintype "passive"))
      (node (ref "C451") (pin "1") (pinfunction "1_1") (pintype "passive"))
      (node (ref "R606") (pin "1") (pinfunction "1_1") (pintype "passive"))
      (node (ref "R606") (pin "2") (pinfunction "1_2") (pintype "passive"))
      (node (ref "U2") (pin "1") (pinfunction "VO2_1") (pintype "bidirectional"))
      (node (ref "U202") (pin "11") (pinfunction "VCC_HI_11") (pintype "power_in"))
      (node (ref "U401") (pin "23") (pinfunction "VDD3-1_23") (pintype "power_in"))
      (node (ref "U401") (pin "43") (pinfunction "VDD3-2_43") (pintype "power_in"))
      (node (ref "U401") (pin "49") (pinfunction "VBAT_49") (pintype "power_in"))
      (node (ref "U401") (pin "51") (pinfunction "VDD3-3_51") (pintype "power_in"))
      (node (ref "U401") (pin "63") (pinfunction "VREF_63") (pintype "input"))
      (node (ref "U401") (pin "7") (pinfunction "VDDA3_7") (pintype "power_in"))
    )
    (net (code "51") (name "5V") (class "Default")
      (node (ref "C010") (pin "1") (pinfunction "1_1") (pintype "passive"))
      (node (ref "C205") (pin "1") (pinfunction "1_1") (pintype "passive"))
      (node (ref "D501") (pin "A") (pinfunction "A_A") (pintype "passive"))
      (node (ref "D502") (pin "A") (pinfunction "A_A") (pintype "passive"))
      (node (ref "J001") (pin "3") (pinfunction "3_3") (pintype "passive"))
      (node (ref "J002") (pin "3") (pinfunction "3_3") (pintype "passive"))
      (node (ref "U2") (pin "3") (pinfunction "EN2_3") (pintype "bidirectional"))
      (node (ref "U2") (pin "4") (pinfunction "EN1_4") (pintype "bidirectional"))
      (node (ref "U2") (pin "5") (pinfunction "VIN_5") (pintype "bidirectional"))
      (node (ref "U501") (pin "20") (pinfunction "VCC_20") (pintype "power_in"))
      (node (ref "U501") (pin "4") (pinfunction "VCCIO_4") (pintype "power_in"))
    )
    (net (code "52") (name "GND") (class "Default")
      (node (ref "C010") (pin "2") (pinfunction "2_2") (pintype "passive"))
      (node (ref "C201") (pin "1") (pinfunction "1_1") (pintype "passive"))
      (node (ref "C201") (pin "2") (pinfunction "1_2") (pintype "passive"))
      (node (ref "C205") (pin "2") (pinfunction "2_2") (pintype "passive"))
      (node (ref "C215") (pin "2") (pinfunction "2_2") (pintype "passive"))
      (node (ref "C423") (pin "2") (pinfunction "2_2") (pintype "passive"))
      (node (ref "C443") (pin "2") (pinfunction "2_2") (pintype "passive"))
      (node (ref "C451") (pin "2") (pinfunction "2_2") (pintype "passive"))
      (node (ref "C461") (pin "1") (pinfunction "1_1") (pintype "passive"))
      (node (ref "C461") (pin "2") (pinfunction "1_2") (pintype "passive"))
      (node (ref "J001") (pin "4") (pinfunction "4_4") (pintype "passive"))
      (node (ref "J002") (pin "4") (pinfunction "4_4") (pintype "passive"))
      (node (ref "J201") (pin "GND") (pinfunction "GND_GND") (pintype "bidirectional"))
      (node (ref "J202") (pin "1") (pinfunction "1_1") (pintype "passive"))
      (node (ref "JP1") (pin "P$1") (pinfunction "P$1_P$1") (pintype "bidirectional"))
      (node (ref "JP2") (pin "P$1") (pinfunction "P$1_P$1") (pintype "bidirectional"))
      (node (ref "JP3") (pin "P$1") (pinfunction "P$1_P$1") (pintype "bidirectional"))
      (node (ref "JP4") (pin "P$1") (pinfunction "P$1_P$1") (pintype "bidirectional"))
      (node (ref "S429") (pin "P$1") (pinfunction "1_P$1") (pintype "bidirectional"))
      (node (ref "S458") (pin "P$2") (pinfunction "2_P$2") (pintype "bidirectional"))
      (node (ref "U2") (pin "2") (pinfunction "GND_2") (pintype "bidirectional"))
      (node (ref "U202") (pin "6") (pinfunction "GND_6") (pintype "power_in"))
      (node (ref "U401") (pin "18") (pinfunction "VSS_18") (pintype "power_in"))
      (node (ref "U401") (pin "25") (pinfunction "VSS_25") (pintype "power_in"))
      (node (ref "U401") (pin "42") (pinfunction "VSS_42") (pintype "power_in"))
      (node (ref "U401") (pin "50") (pinfunction "VSS_50") (pintype "power_in"))
      (node (ref "U401") (pin "59") (pinfunction "VSSA_59") (pintype "power_in"))
      (node (ref "U401") (pin "6") (pinfunction "VSS_6") (pintype "power_in"))
      (node (ref "U501") (pin "18") (pinfunction "GND18_18") (pintype "power_in"))
      (node (ref "U501") (pin "21") (pinfunction "GND21_21") (pintype "power_in"))
      (node (ref "U501") (pin "25") (pinfunction "AGND_25") (pintype "power_in"))
      (node (ref "U501") (pin "26") (pinfunction "TEST_26") (pintype "input"))
      (node (ref "U501") (pin "7") (pinfunction "GND7_7") (pintype "power_in"))
      (node (ref "Y1") (pin "2") (pinfunction "GND_2") (pintype "passive"))
      (node (ref "Y1") (pin "4") (pinfunction "GND_4") (pintype "passive"))
    )
    (net (code "53") (name "Net-(R500A-2)") (class "Default")
      (node (ref "D502") (pin "C") (pinfunction "C_C") (pintype "passive"))
      (node (ref "R500") (pin "4") (pinfunction "2_4") (pintype "passive"))
    )
    (net (code "54") (name "Net-(R500B-1)") (class "Default")
      (node (ref "R500") (pin "2") (pinfunction "1_2") (pintype "passive"))
      (node (ref "U501") (pin "23") (pinfunction "TXLED_23") (pintype "input"))
    )
    (net (code "55") (name "Net-(R500B-2)") (class "Default")
      (node (ref "D501") (pin "C") (pinfunction "C_C") (pintype "passive"))
      (node (ref "R500") (pin "3") (pinfunction "2_3") (pintype "passive"))
    )
    (net (code "56") (name "Net-(U501-DTR)") (class "Default")
      (node (ref "C502") (pin "2") (pinfunction "2_2") (pintype "passive"))
      (node (ref "U501") (pin "2") (pinfunction "DTR_2") (pintype "output"))
    )
    (net (code "57") (name "Net-(U501-RXLED)") (class "Default")
      (node (ref "R500") (pin "1") (pinfunction "1_1") (pintype "passive"))
      (node (ref "U501") (pin "22") (pinfunction "RXLED_22") (pintype "input"))
    )
    (net (code "58") (name "unconnected-(U401-(CAP1.3{slash}MISO1{slash}MAT1.3)P0.18-Pad53)") (class "Default")
      (node (ref "U401") (pin "53") (pinfunction "(CAP1.3/MISO1/MAT1.3)P0.18_53") (pintype "bidirectional"))
    )
    (net (code "59") (name "unconnected-(U401-(DSR1{slash}MAT1.0{slash}AD1.3)P0.12-Pad38)") (class "Default")
      (node (ref "U401") (pin "38") (pinfunction "(DSR1/MAT1.0/AD1.3)P0.12_38") (pintype "bidirectional"))
    )
    (net (code "60") (name "unconnected-(U401-(MAT1.2{slash}MOSI1{slash}CAP1.2)P0.19-Pad54)") (class "Default")
      (node (ref "U401") (pin "54") (pinfunction "(MAT1.2/MOSI1/CAP1.2)P0.19_54") (pintype "bidirectional"))
    )
    (net (code "61") (name "unconnected-(U401-(MAT1.3{slash}SSEL1{slash}EINT3)P0.20-Pad55)") (class "Default")
      (node (ref "U401") (pin "55") (pinfunction "(MAT1.3/SSEL1/EINT3)P0.20_55") (pintype "bidirectional"))
    )
    (net (code "62") (name "unconnected-(U401-(MISO0{slash}MAT0.1{slash}A0.7)P0.5-Pad29)") (class "Default")
      (node (ref "U401") (pin "29") (pinfunction "(MISO0/MAT0.1/A0.7)P0.5_29") (pintype "bidirectional"))
    )
    (net (code "63") (name "unconnected-(U401-(SCK0{slash}CAP0.1{slash}AD0.6)P0.4-Pad27)") (class "Default")
      (node (ref "U401") (pin "27") (pinfunction "(SCK0/CAP0.1/AD0.6)P0.4_27") (pintype "bidirectional"))
    )
    (net (code "64") (name "unconnected-(U401-(SCL0{slash}CAP0.0)P0.2-Pad22)") (class "Default")
      (node (ref "U401") (pin "22") (pinfunction "(SCL0/CAP0.0)P0.2_22") (pintype "bidirectional"))
    )
    (net (code "65") (name "unconnected-(U401-(SDA0{slash}MAT0.0{slash}EINT1)P0.3-Pad26)") (class "Default")
      (node (ref "U401") (pin "26") (pinfunction "(SDA0/MAT0.0/EINT1)P0.3_26") (pintype "bidirectional"))
    )
    (net (code "66") (name "unconnected-(U401-P0.23-Pad58)") (class "Default")
      (node (ref "U401") (pin "58") (pinfunction "P0.23_58") (pintype "bidirectional"))
    )
    (net (code "67") (name "unconnected-(U401-P1.16(TRACEPKT0)-Pad16)") (class "Default")
      (node (ref "U401") (pin "16") (pinfunction "P1.16(TRACEPKT0)_16") (pintype "bidirectional"))
    )
    (net (code "68") (name "unconnected-(U401-P1.17(TRACEPKT1)-Pad12)") (class "Default")
      (node (ref "U401") (pin "12") (pinfunction "P1.17(TRACEPKT1)_12") (pintype "bidirectional"))
    )
    (net (code "69") (name "unconnected-(U401-P1.18(TRACEPKT2)-Pad8)") (class "Default")
      (node (ref "U401") (pin "8") (pinfunction "P1.18(TRACEPKT2)_8") (pintype "bidirectional"))
    )
    (net (code "70") (name "unconnected-(U401-P1.19(TRACEPKT3)-Pad4)") (class "Default")
      (node (ref "U401") (pin "4") (pinfunction "P1.19(TRACEPKT3)_4") (pintype "bidirectional"))
    )
    (net (code "71") (name "unconnected-(U401-P1.20(TRACESYNC)-Pad48)") (class "Default")
      (node (ref "U401") (pin "48") (pinfunction "P1.20(TRACESYNC)_48") (pintype "bidirectional"))
    )
    (net (code "72") (name "unconnected-(U401-P1.21(PIPESTAT0)-Pad44)") (class "Default")
      (node (ref "U401") (pin "44") (pinfunction "P1.21(PIPESTAT0)_44") (pintype "bidirectional"))
    )
    (net (code "73") (name "unconnected-(U401-P1.22(PIPESTAT1)-Pad40)") (class "Default")
      (node (ref "U401") (pin "40") (pinfunction "P1.22(PIPESTAT1)_40") (pintype "bidirectional"))
    )
    (net (code "74") (name "unconnected-(U401-P1.23(PIPESTAT2)-Pad36)") (class "Default")
      (node (ref "U401") (pin "36") (pinfunction "P1.23(PIPESTAT2)_36") (pintype "bidirectional"))
    )
    (net (code "75") (name "unconnected-(U401-P1.24(TRACECLK)-Pad32)") (class "Default")
      (node (ref "U401") (pin "32") (pinfunction "P1.24(TRACECLK)_32") (pintype "bidirectional"))
    )
    (net (code "76") (name "unconnected-(U401-P1.25(EXTIN0)-Pad28)") (class "Default")
      (node (ref "U401") (pin "28") (pinfunction "P1.25(EXTIN0)_28") (pintype "bidirectional"))
    )
    (net (code "77") (name "unconnected-(U401-P1.26(RTCK)-Pad24)") (class "Default")
      (node (ref "U401") (pin "24") (pinfunction "P1.26(RTCK)_24") (pintype "bidirectional"))
    )
    (net (code "78") (name "unconnected-(U401-P1.27(TDO)-Pad64)") (class "Default")
      (node (ref "U401") (pin "64") (pinfunction "P1.27(TDO)_64") (pintype "bidirectional"))
    )
    (net (code "79") (name "unconnected-(U401-P1.28(TDI)-Pad60)") (class "Default")
      (node (ref "U401") (pin "60") (pinfunction "P1.28(TDI)_60") (pintype "bidirectional"))
    )
    (net (code "80") (name "unconnected-(U401-P1.29(TCK)-Pad56)") (class "Default")
      (node (ref "U401") (pin "56") (pinfunction "P1.29(TCK)_56") (pintype "bidirectional"))
    )
    (net (code "81") (name "unconnected-(U401-P1.30(TMS)-Pad52)") (class "Default")
      (node (ref "U401") (pin "52") (pinfunction "P1.30(TMS)_52") (pintype "bidirectional"))
    )
    (net (code "82") (name "unconnected-(U401-P1.31({slash}TRST)-Pad20)") (class "Default")
      (node (ref "U401") (pin "20") (pinfunction "P1.31(/TRST)_20") (pintype "bidirectional"))
    )
    (net (code "83") (name "unconnected-(U401-RTXC1-Pad3)") (class "Default")
      (node (ref "U401") (pin "3") (pinfunction "RTXC1_3") (pintype "input"))
    )
    (net (code "84") (name "unconnected-(U401-RTXC2-Pad5)") (class "Default")
      (node (ref "U401") (pin "5") (pinfunction "RTXC2_5") (pintype "output"))
    )
    (net (code "85") (name "unconnected-(U501-3V3OUT-Pad17)") (class "Default")
      (node (ref "U501") (pin "17") (pinfunction "3V3OUT_17") (pintype "output"))
    )
    (net (code "86") (name "unconnected-(U501-CTS-Pad11)") (class "Default")
      (node (ref "U501") (pin "11") (pinfunction "CTS_11") (pintype "input"))
    )
    (net (code "87") (name "unconnected-(U501-DCD-Pad10)") (class "Default")
      (node (ref "U501") (pin "10") (pinfunction "DCD_10") (pintype "input"))
    )
    (net (code "88") (name "unconnected-(U501-DSR-Pad9)") (class "Default")
      (node (ref "U501") (pin "9") (pinfunction "DSR_9") (pintype "input"))
    )
    (net (code "89") (name "unconnected-(U501-OSCI-Pad27)") (class "Default")
      (node (ref "U501") (pin "27") (pinfunction "OSCI_27") (pintype "input"))
    )
    (net (code "90") (name "unconnected-(U501-OSCO-Pad28)") (class "Default")
      (node (ref "U501") (pin "28") (pinfunction "OSCO_28") (pintype "output"))
    )
    (net (code "91") (name "unconnected-(U501-PWREN-Pad14)") (class "Default")
      (node (ref "U501") (pin "14") (pinfunction "PWREN_14") (pintype "input"))
    )
    (net (code "92") (name "unconnected-(U501-RESET-Pad19)") (class "Default")
      (node (ref "U501") (pin "19") (pinfunction "RESET_19") (pintype "input"))
    )
    (net (code "93") (name "unconnected-(U501-RI-Pad6)") (class "Default")
      (node (ref "U501") (pin "6") (pinfunction "RI_6") (pintype "input"))
    )
    (net (code "94") (name "unconnected-(U501-RTS-Pad3)") (class "Default")
      (node (ref "U501") (pin "3") (pinfunction "RTS_3") (pintype "output"))
    )
    (net (code "95") (name "unconnected-(U501-SLEEP-Pad12)") (class "Default")
      (node (ref "U501") (pin "12") (pinfunction "SLEEP_12") (pintype "input"))
    )
    (net (code "96") (name "unconnected-(U501-TXDEN-Pad13)") (class "Default")
      (node (ref "U501") (pin "13") (pinfunction "TXDEN_13") (pintype "input"))
    )
  )
)
